# R650X.net
KiCad netlist of a schematic drawn in EAGLE
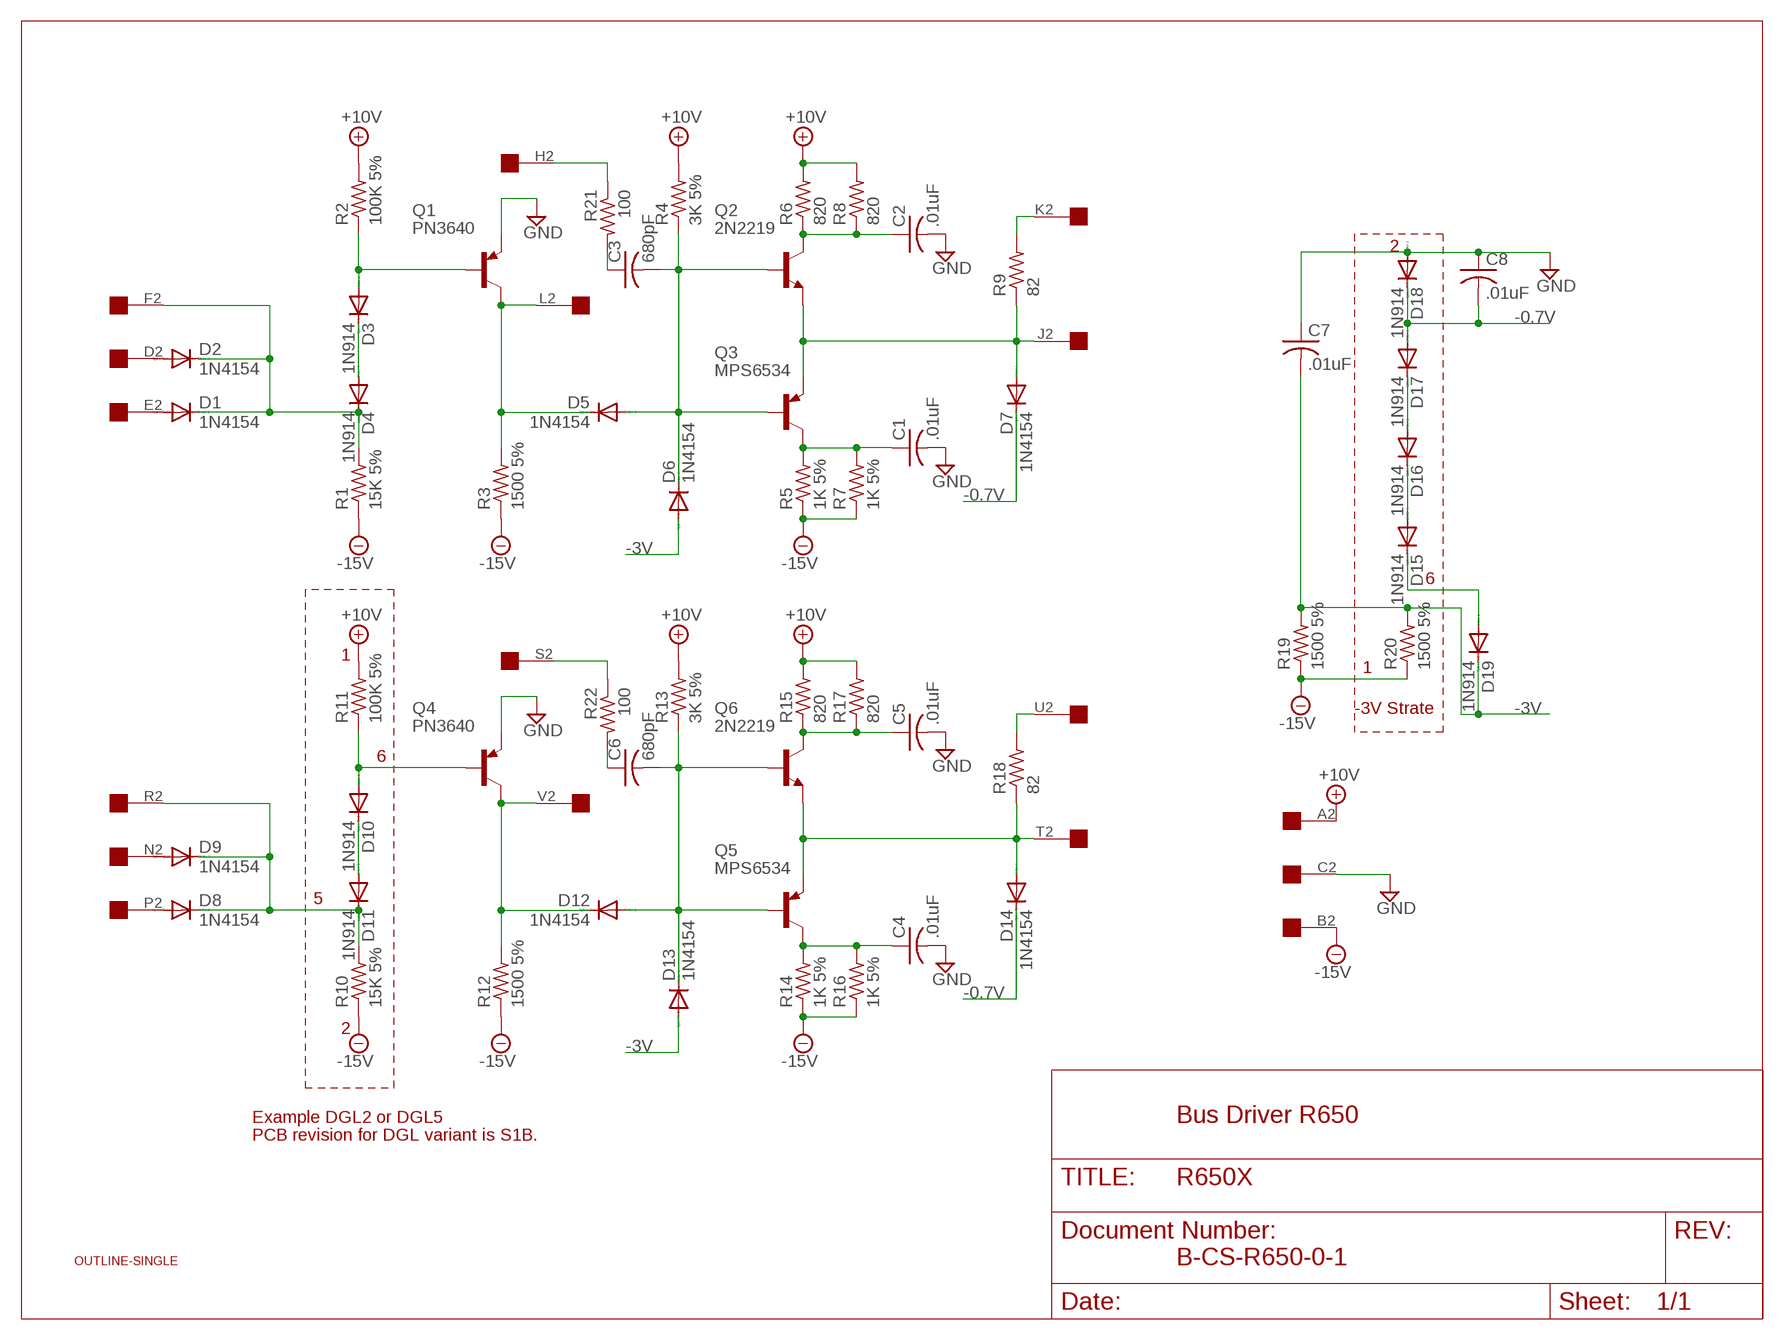
[diagram p0: schematic, sheet 1]

(export (version "E")
  (design (tool "Eeschema 10.0.6"))
  (components
    (comp (ref "C1")
      (value ".01uF")
      (footprint "eagle-import:C102-043X133")
      (libsource (lib "eagle-import") (part "C-US102-043X133"))
    )
    (comp (ref "C2")
      (value ".01uF")
      (footprint "eagle-import:C102-043X133")
      (libsource (lib "eagle-import") (part "C-US102-043X133"))
    )
    (comp (ref "C3")
      (value "680pF")
      (footprint "eagle-import:C102-043X133")
      (libsource (lib "eagle-import") (part "C-US102-043X133"))
    )
    (comp (ref "C4")
      (value ".01uF")
      (footprint "eagle-import:C102-043X133")
      (libsource (lib "eagle-import") (part "C-US102-043X133"))
    )
    (comp (ref "C5")
      (value ".01uF")
      (footprint "eagle-import:C102-043X133")
      (libsource (lib "eagle-import") (part "C-US102-043X133"))
    )
    (comp (ref "C6")
      (value "680pF")
      (footprint "eagle-import:C102-043X133")
      (libsource (lib "eagle-import") (part "C-US102-043X133"))
    )
    (comp (ref "C7")
      (value ".01uF")
      (footprint "eagle-import:C102-043X133")
      (libsource (lib "eagle-import") (part "C-US102-043X133"))
    )
    (comp (ref "C8")
      (value ".01uF")
      (footprint "eagle-import:C102-043X133")
      (libsource (lib "eagle-import") (part "C-US102-043X133"))
    )
    (comp (ref "D1")
      (value "1N4154")
      (footprint "eagle-import:DO35-10")
      (libsource (lib "eagle-import") (part "1N4148DO35-10"))
    )
    (comp (ref "D2")
      (value "1N4154")
      (footprint "eagle-import:DO35-10")
      (libsource (lib "eagle-import") (part "1N4148DO35-10"))
    )
    (comp (ref "D3")
      (value "1N914")
      (footprint "eagle-import:DO35-10")
      (libsource (lib "eagle-import") (part "1N4148DO35-10"))
    )
    (comp (ref "D4")
      (value "1N914")
      (footprint "eagle-import:DO35-10")
      (libsource (lib "eagle-import") (part "1N4148DO35-10"))
    )
    (comp (ref "D5")
      (value "1N4154")
      (footprint "eagle-import:DO35-10")
      (libsource (lib "eagle-import") (part "1N4148DO35-10"))
    )
    (comp (ref "D6")
      (value "1N4154")
      (footprint "eagle-import:DO35-10")
      (libsource (lib "eagle-import") (part "1N4148DO35-10"))
    )
    (comp (ref "D7")
      (value "1N4154")
      (footprint "eagle-import:DO35-10")
      (libsource (lib "eagle-import") (part "1N4148DO35-10"))
    )
    (comp (ref "D8")
      (value "1N4154")
      (footprint "eagle-import:DO35-10")
      (libsource (lib "eagle-import") (part "1N4148DO35-10"))
    )
    (comp (ref "D9")
      (value "1N4154")
      (footprint "eagle-import:DO35-10")
      (libsource (lib "eagle-import") (part "1N4148DO35-10"))
    )
    (comp (ref "D10")
      (value "1N914")
      (footprint "eagle-import:DO35-10")
      (libsource (lib "eagle-import") (part "1N4148DO35-10"))
    )
    (comp (ref "D11")
      (value "1N914")
      (footprint "eagle-import:DO35-10")
      (libsource (lib "eagle-import") (part "1N4148DO35-10"))
    )
    (comp (ref "D12")
      (value "1N4154")
      (footprint "eagle-import:DO35-10")
      (libsource (lib "eagle-import") (part "1N4148DO35-10"))
    )
    (comp (ref "D13")
      (value "1N4154")
      (footprint "eagle-import:DO35-10")
      (libsource (lib "eagle-import") (part "1N4148DO35-10"))
    )
    (comp (ref "D14")
      (value "1N4154")
      (footprint "eagle-import:DO35-10")
      (libsource (lib "eagle-import") (part "1N4148DO35-10"))
    )
    (comp (ref "D15")
      (value "1N914")
      (footprint "eagle-import:DO35-10")
      (libsource (lib "eagle-import") (part "1N4148DO35-10"))
    )
    (comp (ref "D16")
      (value "1N914")
      (footprint "eagle-import:DO35-10")
      (libsource (lib "eagle-import") (part "1N4148DO35-10"))
    )
    (comp (ref "D17")
      (value "1N914")
      (footprint "eagle-import:DO35-10")
      (libsource (lib "eagle-import") (part "1N4148DO35-10"))
    )
    (comp (ref "D18")
      (value "1N914")
      (footprint "eagle-import:DO35-10")
      (libsource (lib "eagle-import") (part "1N4148DO35-10"))
    )
    (comp (ref "D19")
      (value "1N914")
      (footprint "eagle-import:DO35-10")
      (libsource (lib "eagle-import") (part "1N4148DO35-10"))
    )
    (comp (ref "Q1")
      (value "PN3640")
      (footprint "eagle-import:TO39")
      (libsource (lib "eagle-import") (part "2N3637"))
    )
    (comp (ref "Q2")
      (value "2N2219")
      (footprint "eagle-import:TO5")
      (libsource (lib "eagle-import") (part "2N2219"))
    )
    (comp (ref "Q3")
      (value "MPS6534")
      (footprint "eagle-import:TO39")
      (libsource (lib "eagle-import") (part "2N3637"))
    )
    (comp (ref "Q4")
      (value "PN3640")
      (footprint "eagle-import:TO39")
      (libsource (lib "eagle-import") (part "2N3637"))
    )
    (comp (ref "Q5")
      (value "MPS6534")
      (footprint "eagle-import:TO39")
      (libsource (lib "eagle-import") (part "2N3637"))
    )
    (comp (ref "Q6")
      (value "2N2219")
      (footprint "eagle-import:TO5")
      (libsource (lib "eagle-import") (part "2N2219"))
    )
    (comp (ref "R1")
      (value "15K 5%")
      (footprint "eagle-import:0207_10")
      (libsource (lib "eagle-import") (part "R-US_0207/10"))
    )
    (comp (ref "R2")
      (value "100K 5%")
      (footprint "eagle-import:0207_10")
      (libsource (lib "eagle-import") (part "R-US_0207/10"))
    )
    (comp (ref "R3")
      (value "1500 5%")
      (footprint "eagle-import:0207_10")
      (libsource (lib "eagle-import") (part "R-US_0207/10"))
    )
    (comp (ref "R4")
      (value "3K 5%")
      (footprint "eagle-import:0207_10")
      (libsource (lib "eagle-import") (part "R-US_0207/10"))
    )
    (comp (ref "R5")
      (value "1K 5%")
      (footprint "eagle-import:0207_10")
      (libsource (lib "eagle-import") (part "R-US_0207/10"))
    )
    (comp (ref "R6")
      (value "820")
      (footprint "eagle-import:0207_10")
      (libsource (lib "eagle-import") (part "R-US_0207/10"))
    )
    (comp (ref "R7")
      (value "1K 5%")
      (footprint "eagle-import:0207_10")
      (libsource (lib "eagle-import") (part "R-US_0207/10"))
    )
    (comp (ref "R8")
      (value "820")
      (footprint "eagle-import:0207_10")
      (libsource (lib "eagle-import") (part "R-US_0207/10"))
    )
    (comp (ref "R9")
      (value "82")
      (footprint "eagle-import:0207_10")
      (libsource (lib "eagle-import") (part "R-US_0207/10"))
    )
    (comp (ref "R10")
      (value "15K 5%")
      (footprint "eagle-import:0207_10")
      (libsource (lib "eagle-import") (part "R-US_0207/10"))
    )
    (comp (ref "R11")
      (value "100K 5%")
      (footprint "eagle-import:0207_10")
      (libsource (lib "eagle-import") (part "R-US_0207/10"))
    )
    (comp (ref "R12")
      (value "1500 5%")
      (footprint "eagle-import:0207_10")
      (libsource (lib "eagle-import") (part "R-US_0207/10"))
    )
    (comp (ref "R13")
      (value "3K 5%")
      (footprint "eagle-import:0207_10")
      (libsource (lib "eagle-import") (part "R-US_0207/10"))
    )
    (comp (ref "R14")
      (value "1K 5%")
      (footprint "eagle-import:0207_10")
      (libsource (lib "eagle-import") (part "R-US_0207/10"))
    )
    (comp (ref "R15")
      (value "820")
      (footprint "eagle-import:0207_10")
      (libsource (lib "eagle-import") (part "R-US_0207/10"))
    )
    (comp (ref "R16")
      (value "1K 5%")
      (footprint "eagle-import:0207_10")
      (libsource (lib "eagle-import") (part "R-US_0207/10"))
    )
    (comp (ref "R17")
      (value "820")
      (footprint "eagle-import:0207_10")
      (libsource (lib "eagle-import") (part "R-US_0207/10"))
    )
    (comp (ref "R18")
      (value "82")
      (footprint "eagle-import:0207_10")
      (libsource (lib "eagle-import") (part "R-US_0207/10"))
    )
    (comp (ref "R19")
      (value "1500 5%")
      (footprint "eagle-import:0207_10")
      (libsource (lib "eagle-import") (part "R-US_0207/10"))
    )
    (comp (ref "R20")
      (value "1500 5%")
      (footprint "eagle-import:0207_10")
      (libsource (lib "eagle-import") (part "R-US_0207/10"))
    )
    (comp (ref "R21")
      (value "100")
      (footprint "eagle-import:0207_10")
      (libsource (lib "eagle-import") (part "R-US_0207/10"))
    )
    (comp (ref "R22")
      (value "100")
      (footprint "eagle-import:0207_10")
      (libsource (lib "eagle-import") (part "R-US_0207/10"))
    )
    (comp (ref "U$1")
      (value "OUTLINE-SINGLE")
      (footprint "eagle-import:SINGLE")
      (libsource (lib "eagle-import") (part "OUTLINE-SINGLE"))
    )
    (comp (ref "U$2")
      (value "EDGE-1")
      (footprint "eagle-import:EDGE-CON1")
      (libsource (lib "eagle-import") (part "EDGE-1"))
    )
  )
  (nets
    (net (code "1") (name "+10V") (class "Default")
      (node (ref "R11") (pin "2") (pinfunction "2_2") (pintype "passive"))
      (node (ref "R13") (pin "2") (pinfunction "2_2") (pintype "passive"))
      (node (ref "R15") (pin "2") (pinfunction "2_2") (pintype "passive"))
      (node (ref "R17") (pin "2") (pinfunction "2_2") (pintype "passive"))
      (node (ref "R2") (pin "2") (pinfunction "2_2") (pintype "passive"))
      (node (ref "R4") (pin "2") (pinfunction "2_2") (pintype "passive"))
      (node (ref "R6") (pin "2") (pinfunction "2_2") (pintype "passive"))
      (node (ref "R8") (pin "2") (pinfunction "2_2") (pintype "passive"))
      (node (ref "U$2") (pin "A2") (pinfunction "1_A2") (pintype "bidirectional"))
    )
    (net (code "2") (name "-15V") (class "Default")
      (node (ref "R1") (pin "1") (pinfunction "1_1") (pintype "passive"))
      (node (ref "R10") (pin "1") (pinfunction "1_1") (pintype "passive"))
      (node (ref "R12") (pin "1") (pinfunction "1_1") (pintype "passive"))
      (node (ref "R14") (pin "1") (pinfunction "1_1") (pintype "passive"))
      (node (ref "R16") (pin "1") (pinfunction "1_1") (pintype "passive"))
      (node (ref "R19") (pin "1") (pinfunction "1_1") (pintype "passive"))
      (node (ref "R20") (pin "1") (pinfunction "1_1") (pintype "passive"))
      (node (ref "R3") (pin "1") (pinfunction "1_1") (pintype "passive"))
      (node (ref "R5") (pin "1") (pinfunction "1_1") (pintype "passive"))
      (node (ref "R7") (pin "1") (pinfunction "1_1") (pintype "passive"))
      (node (ref "U$2") (pin "B2") (pinfunction "1_B2") (pintype "bidirectional"))
    )
    (net (code "3") (name "/-0.7V") (class "Default")
      (node (ref "C8") (pin "2") (pinfunction "2_2") (pintype "passive"))
      (node (ref "D14") (pin "C") (pinfunction "C_C") (pintype "passive"))
      (node (ref "D17") (pin "A") (pinfunction "A_A") (pintype "passive"))
      (node (ref "D18") (pin "C") (pinfunction "C_C") (pintype "passive"))
      (node (ref "D7") (pin "C") (pinfunction "C_C") (pintype "passive"))
    )
    (net (code "4") (name "/-3V") (class "Default")
      (node (ref "C7") (pin "2") (pinfunction "2_2") (pintype "passive"))
      (node (ref "D13") (pin "A") (pinfunction "A_A") (pintype "passive"))
      (node (ref "D19") (pin "C") (pinfunction "C_C") (pintype "passive"))
      (node (ref "D6") (pin "A") (pinfunction "A_A") (pintype "passive"))
      (node (ref "R19") (pin "2") (pinfunction "2_2") (pintype "passive"))
      (node (ref "R20") (pin "2") (pinfunction "2_2") (pintype "passive"))
    )
    (net (code "5") (name "GND") (class "Default")
      (node (ref "C1") (pin "2") (pinfunction "2_2") (pintype "passive"))
      (node (ref "C2") (pin "2") (pinfunction "2_2") (pintype "passive"))
      (node (ref "C4") (pin "2") (pinfunction "2_2") (pintype "passive"))
      (node (ref "C5") (pin "2") (pinfunction "2_2") (pintype "passive"))
      (node (ref "C7") (pin "1") (pinfunction "1_1") (pintype "passive"))
      (node (ref "C8") (pin "1") (pinfunction "1_1") (pintype "passive"))
      (node (ref "D18") (pin "A") (pinfunction "A_A") (pintype "passive"))
      (node (ref "Q1") (pin "1") (pinfunction "E_1") (pintype "passive"))
      (node (ref "Q4") (pin "1") (pinfunction "E_1") (pintype "passive"))
      (node (ref "U$2") (pin "C2") (pinfunction "1_C2") (pintype "bidirectional"))
    )
    (net (code "6") (name "Net-(C3-Pad1)") (class "Default")
      (node (ref "C3") (pin "1") (pinfunction "1_1") (pintype "passive"))
      (node (ref "R21") (pin "2") (pinfunction "2_2") (pintype "passive"))
    )
    (net (code "7") (name "Net-(C6-Pad1)") (class "Default")
      (node (ref "C6") (pin "1") (pinfunction "1_1") (pintype "passive"))
      (node (ref "R22") (pin "2") (pinfunction "2_2") (pintype "passive"))
    )
    (net (code "8") (name "Net-(D3-PadC)") (class "Default")
      (node (ref "D3") (pin "C") (pinfunction "C_C") (pintype "passive"))
      (node (ref "D4") (pin "A") (pinfunction "A_A") (pintype "passive"))
    )
    (net (code "9") (name "Net-(D10-PadC)") (class "Default")
      (node (ref "D10") (pin "C") (pinfunction "C_C") (pintype "passive"))
      (node (ref "D11") (pin "A") (pinfunction "A_A") (pintype "passive"))
    )
    (net (code "10") (name "Net-(D15-PadA)") (class "Default")
      (node (ref "D15") (pin "A") (pinfunction "A_A") (pintype "passive"))
      (node (ref "D16") (pin "C") (pinfunction "C_C") (pintype "passive"))
    )
    (net (code "11") (name "Net-(D15-PadC)") (class "Default")
      (node (ref "D15") (pin "C") (pinfunction "C_C") (pintype "passive"))
      (node (ref "D19") (pin "A") (pinfunction "A_A") (pintype "passive"))
    )
    (net (code "12") (name "Net-(D16-PadA)") (class "Default")
      (node (ref "D16") (pin "A") (pinfunction "A_A") (pintype "passive"))
      (node (ref "D17") (pin "C") (pinfunction "C_C") (pintype "passive"))
    )
    (net (code "13") (name "Net-(Q1-B)") (class "Default")
      (node (ref "D3") (pin "A") (pinfunction "A_A") (pintype "passive"))
      (node (ref "Q1") (pin "2") (pinfunction "B_2") (pintype "passive"))
      (node (ref "R2") (pin "1") (pinfunction "1_1") (pintype "passive"))
    )
    (net (code "14") (name "Net-(Q1-C)") (class "Default")
      (node (ref "D5") (pin "C") (pinfunction "C_C") (pintype "passive"))
      (node (ref "Q1") (pin "3") (pinfunction "C_3") (pintype "passive"))
      (node (ref "R3") (pin "2") (pinfunction "2_2") (pintype "passive"))
      (node (ref "U$2") (pin "L2") (pinfunction "1_L2") (pintype "bidirectional"))
    )
    (net (code "15") (name "Net-(Q2-B)") (class "Default")
      (node (ref "C3") (pin "2") (pinfunction "2_2") (pintype "passive"))
      (node (ref "D5") (pin "A") (pinfunction "A_A") (pintype "passive"))
      (node (ref "D6") (pin "C") (pinfunction "C_C") (pintype "passive"))
      (node (ref "Q2") (pin "2") (pinfunction "B_2") (pintype "passive"))
      (node (ref "Q3") (pin "2") (pinfunction "B_2") (pintype "passive"))
      (node (ref "R4") (pin "1") (pinfunction "1_1") (pintype "passive"))
    )
    (net (code "16") (name "Net-(Q2-C)") (class "Default")
      (node (ref "C2") (pin "1") (pinfunction "1_1") (pintype "passive"))
      (node (ref "Q2") (pin "3") (pinfunction "C_3") (pintype "passive"))
      (node (ref "R6") (pin "1") (pinfunction "1_1") (pintype "passive"))
      (node (ref "R8") (pin "1") (pinfunction "1_1") (pintype "passive"))
    )
    (net (code "17") (name "Net-(Q2-E)") (class "Default")
      (node (ref "D7") (pin "A") (pinfunction "A_A") (pintype "passive"))
      (node (ref "Q2") (pin "1") (pinfunction "E_1") (pintype "passive"))
      (node (ref "Q3") (pin "1") (pinfunction "E_1") (pintype "passive"))
      (node (ref "R9") (pin "1") (pinfunction "1_1") (pintype "passive"))
      (node (ref "U$2") (pin "J2") (pinfunction "1_J2") (pintype "bidirectional"))
    )
    (net (code "18") (name "Net-(Q3-C)") (class "Default")
      (node (ref "C1") (pin "1") (pinfunction "1_1") (pintype "passive"))
      (node (ref "Q3") (pin "3") (pinfunction "C_3") (pintype "passive"))
      (node (ref "R5") (pin "2") (pinfunction "2_2") (pintype "passive"))
      (node (ref "R7") (pin "2") (pinfunction "2_2") (pintype "passive"))
    )
    (net (code "19") (name "Net-(Q4-B)") (class "Default")
      (node (ref "D10") (pin "A") (pinfunction "A_A") (pintype "passive"))
      (node (ref "Q4") (pin "2") (pinfunction "B_2") (pintype "passive"))
      (node (ref "R11") (pin "1") (pinfunction "1_1") (pintype "passive"))
    )
    (net (code "20") (name "Net-(Q4-C)") (class "Default")
      (node (ref "D12") (pin "C") (pinfunction "C_C") (pintype "passive"))
      (node (ref "Q4") (pin "3") (pinfunction "C_3") (pintype "passive"))
      (node (ref "R12") (pin "2") (pinfunction "2_2") (pintype "passive"))
      (node (ref "U$2") (pin "V2") (pinfunction "1_V2") (pintype "bidirectional"))
    )
    (net (code "21") (name "Net-(Q5-B)") (class "Default")
      (node (ref "C6") (pin "2") (pinfunction "2_2") (pintype "passive"))
      (node (ref "D12") (pin "A") (pinfunction "A_A") (pintype "passive"))
      (node (ref "D13") (pin "C") (pinfunction "C_C") (pintype "passive"))
      (node (ref "Q5") (pin "2") (pinfunction "B_2") (pintype "passive"))
      (node (ref "Q6") (pin "2") (pinfunction "B_2") (pintype "passive"))
      (node (ref "R13") (pin "1") (pinfunction "1_1") (pintype "passive"))
    )
    (net (code "22") (name "Net-(Q5-C)") (class "Default")
      (node (ref "C4") (pin "1") (pinfunction "1_1") (pintype "passive"))
      (node (ref "Q5") (pin "3") (pinfunction "C_3") (pintype "passive"))
      (node (ref "R14") (pin "2") (pinfunction "2_2") (pintype "passive"))
      (node (ref "R16") (pin "2") (pinfunction "2_2") (pintype "passive"))
    )
    (net (code "23") (name "Net-(Q5-E)") (class "Default")
      (node (ref "D14") (pin "A") (pinfunction "A_A") (pintype "passive"))
      (node (ref "Q5") (pin "1") (pinfunction "E_1") (pintype "passive"))
      (node (ref "Q6") (pin "1") (pinfunction "E_1") (pintype "passive"))
      (node (ref "R18") (pin "1") (pinfunction "1_1") (pintype "passive"))
      (node (ref "U$2") (pin "T2") (pinfunction "1_T2") (pintype "bidirectional"))
    )
    (net (code "24") (name "Net-(Q6-C)") (class "Default")
      (node (ref "C5") (pin "1") (pinfunction "1_1") (pintype "passive"))
      (node (ref "Q6") (pin "3") (pinfunction "C_3") (pintype "passive"))
      (node (ref "R15") (pin "1") (pinfunction "1_1") (pintype "passive"))
      (node (ref "R17") (pin "1") (pinfunction "1_1") (pintype "passive"))
    )
    (net (code "25") (name "Net-(U$2D-1)") (class "Default")
      (node (ref "D2") (pin "A") (pinfunction "A_A") (pintype "passive"))
      (node (ref "U$2") (pin "D2") (pinfunction "1_D2") (pintype "bidirectional"))
    )
    (net (code "26") (name "Net-(U$2E-1)") (class "Default")
      (node (ref "D1") (pin "A") (pinfunction "A_A") (pintype "passive"))
      (node (ref "U$2") (pin "E2") (pinfunction "1_E2") (pintype "bidirectional"))
    )
    (net (code "27") (name "Net-(U$2F-1)") (class "Default")
      (node (ref "D1") (pin "C") (pinfunction "C_C") (pintype "passive"))
      (node (ref "D2") (pin "C") (pinfunction "C_C") (pintype "passive"))
      (node (ref "D4") (pin "C") (pinfunction "C_C") (pintype "passive"))
      (node (ref "R1") (pin "2") (pinfunction "2_2") (pintype "passive"))
      (node (ref "U$2") (pin "F2") (pinfunction "1_F2") (pintype "bidirectional"))
    )
    (net (code "28") (name "Net-(U$2G-1)") (class "Default")
      (node (ref "R21") (pin "1") (pinfunction "1_1") (pintype "passive"))
      (node (ref "U$2") (pin "H2") (pinfunction "1_H2") (pintype "bidirectional"))
    )
    (net (code "29") (name "Net-(U$2I-1)") (class "Default")
      (node (ref "R9") (pin "2") (pinfunction "2_2") (pintype "passive"))
      (node (ref "U$2") (pin "K2") (pinfunction "1_K2") (pintype "bidirectional"))
    )
    (net (code "30") (name "Net-(U$2L-1)") (class "Default")
      (node (ref "D9") (pin "A") (pinfunction "A_A") (pintype "passive"))
      (node (ref "U$2") (pin "N2") (pinfunction "1_N2") (pintype "bidirectional"))
    )
    (net (code "31") (name "Net-(U$2M-1)") (class "Default")
      (node (ref "D8") (pin "A") (pinfunction "A_A") (pintype "passive"))
      (node (ref "U$2") (pin "P2") (pinfunction "1_P2") (pintype "bidirectional"))
    )
    (net (code "32") (name "Net-(U$2N-1)") (class "Default")
      (node (ref "D11") (pin "C") (pinfunction "C_C") (pintype "passive"))
      (node (ref "D8") (pin "C") (pinfunction "C_C") (pintype "passive"))
      (node (ref "D9") (pin "C") (pinfunction "C_C") (pintype "passive"))
      (node (ref "R10") (pin "2") (pinfunction "2_2") (pintype "passive"))
      (node (ref "U$2") (pin "R2") (pinfunction "1_R2") (pintype "bidirectional"))
    )
    (net (code "33") (name "Net-(U$2O-1)") (class "Default")
      (node (ref "R22") (pin "1") (pinfunction "1_1") (pintype "passive"))
      (node (ref "U$2") (pin "S2") (pinfunction "1_S2") (pintype "bidirectional"))
    )
    (net (code "34") (name "Net-(U$2Q-1)") (class "Default")
      (node (ref "R18") (pin "2") (pinfunction "2_2") (pintype "passive"))
      (node (ref "U$2") (pin "U2") (pinfunction "1_U2") (pintype "bidirectional"))
    )
  )
)
